# Granulobot_V10.net
KiCad netlist of a schematic drawn in EAGLE
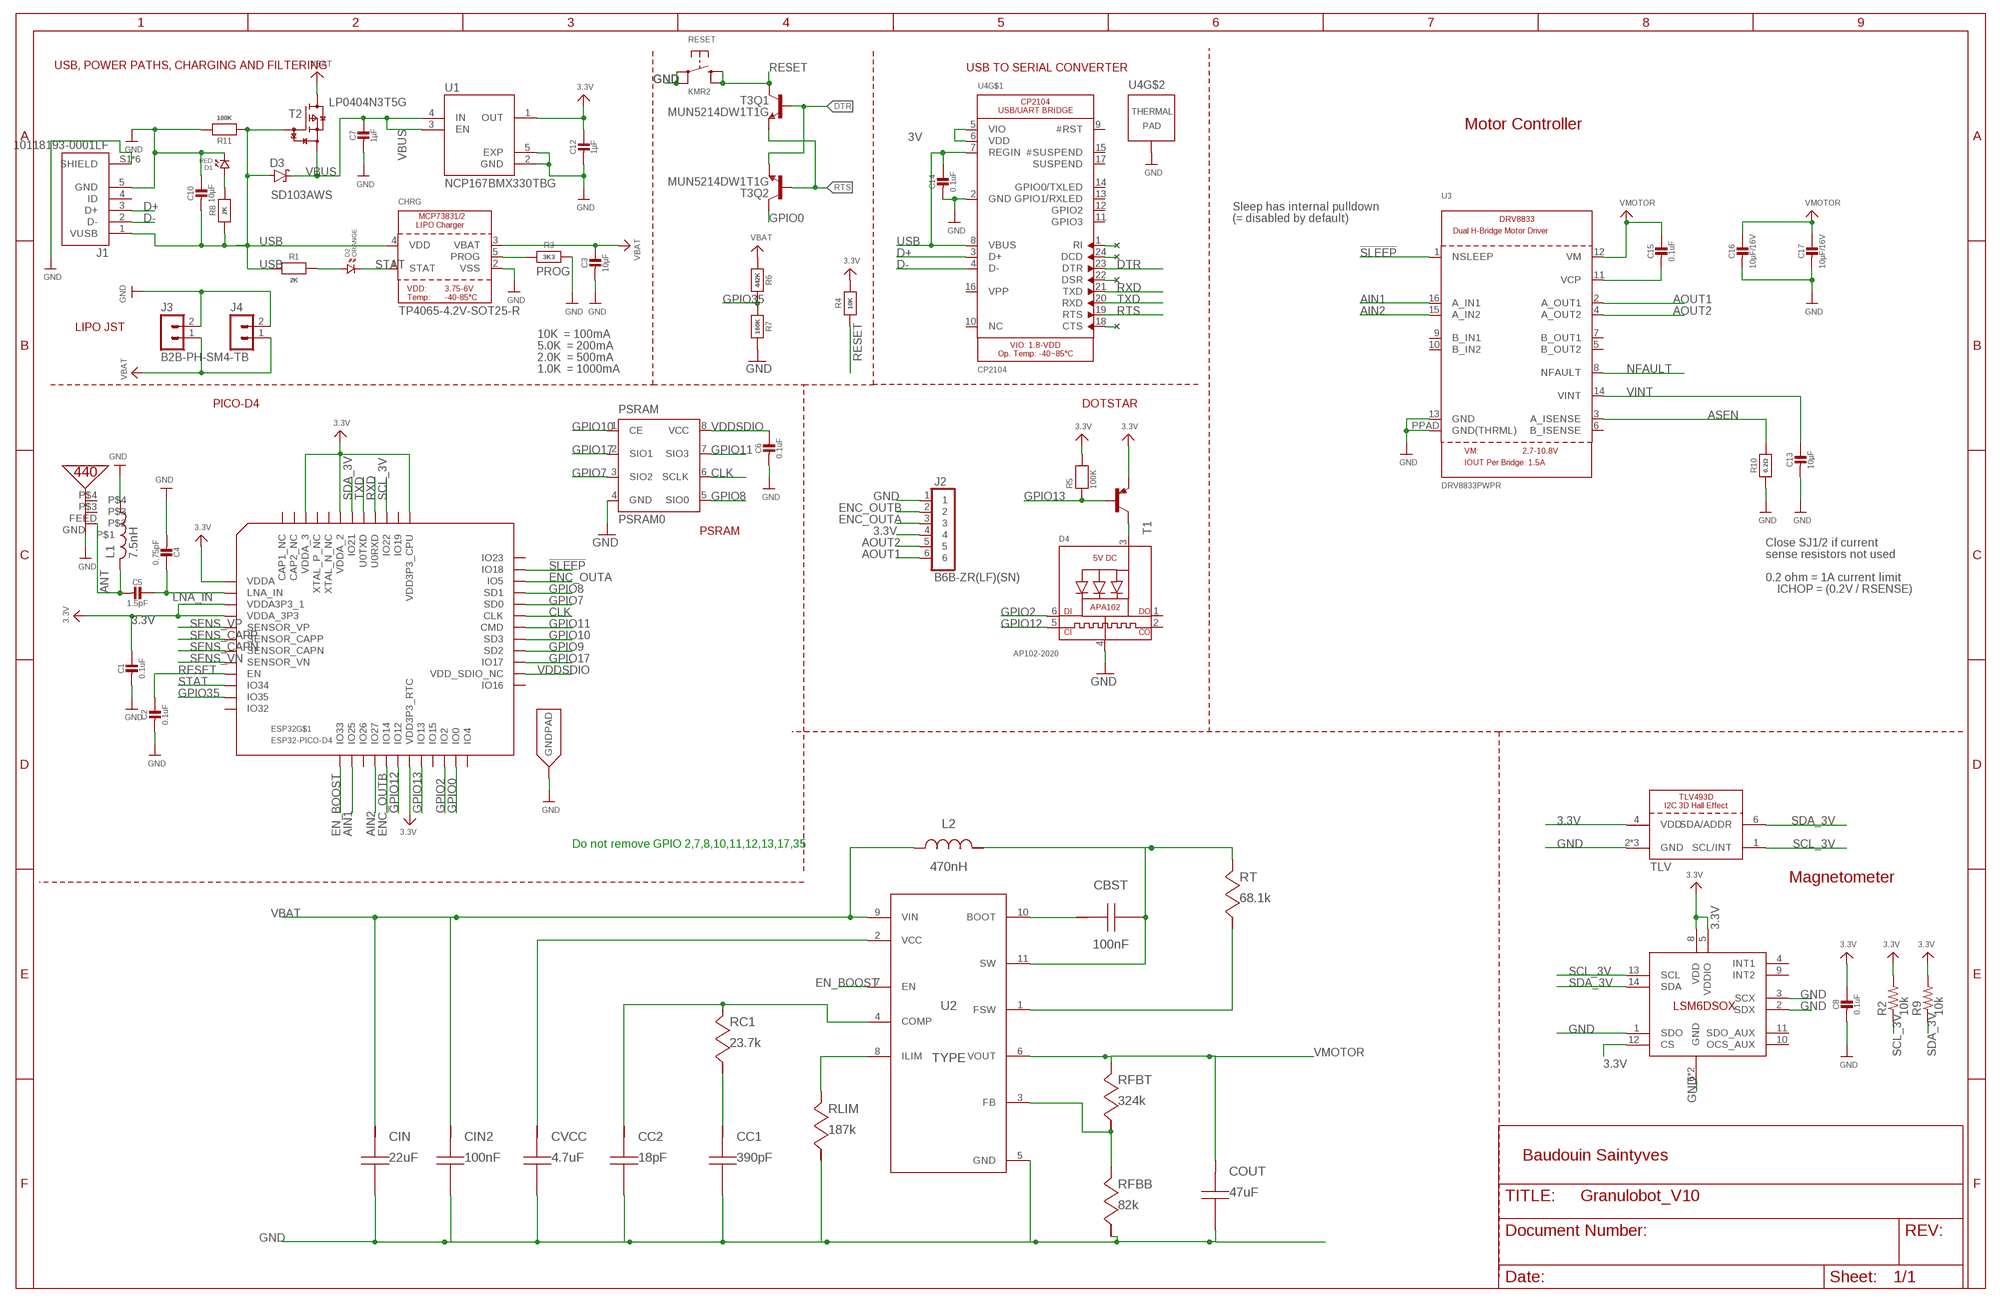
[diagram p0: schematic, sheet 1]

(export (version "E")
  (design (tool "Eeschema 10.0.6"))
  (components
    (comp (ref "ANT")
      (value "PRO-OB-440")
      (footprint "eagle-import:PRO-OB-440")
      (libsource (lib "eagle-import") (part "PRO-OB-440"))
    )
    (comp (ref "C1")
      (value "0.1uF")
      (footprint "eagle-import:_0402MP")
      (fields (field (name "MF") "MULTICOMP PRO") (field (name "MPN") "MC0402X104K250CT"))
      (libsource (lib "eagle-import") (part "CAP_CERAMIC_0402MP"))
    )
    (comp (ref "C2")
      (value "0.1uF")
      (footprint "eagle-import:_0402MP")
      (fields (field (name "MF") "MULTICOMP PRO") (field (name "MPN") "MC0402X104K250CT"))
      (libsource (lib "eagle-import") (part "CAP_CERAMIC_0402MP"))
    )
    (comp (ref "C3")
      (value "10µF")
      (footprint "eagle-import:_0603MP")
      (fields (field (name "MF") "SAMSUNG ELECTRO-MECHANICS") (field (name "MPN") "CL10A106KP8NNNC"))
      (libsource (lib "eagle-import") (part "CAP_CERAMIC_0603MP"))
    )
    (comp (ref "C4")
      (value "0.75pF")
      (footprint "eagle-import:_0402MP")
      (fields (field (name "MF") "MURATA") (field (name "MPN") "GJM1555C1HR75BB01D"))
      (libsource (lib "eagle-import") (part "CAP_CERAMIC_0402MP"))
    )
    (comp (ref "C5")
      (value "1.5pF")
      (footprint "eagle-import:_0402MP")
      (fields (field (name "MF") "TDK") (field (name "MPN") "C1005C0G1H1R5B050BA"))
      (libsource (lib "eagle-import") (part "CAP_CERAMIC_0402MP"))
    )
    (comp (ref "C6")
      (value "0.1uF")
      (footprint "eagle-import:_0402MP")
      (fields (field (name "MF") "MULTICOMP PRO") (field (name "MPN") "MC0402X104K250CT"))
      (libsource (lib "eagle-import") (part "CAP_CERAMIC_0402MP"))
    )
    (comp (ref "C7")
      (value "1µF")
      (footprint "eagle-import:_0402MP")
      (fields (field (name "MF") "MURATA") (field (name "MPN") "GRT155R70J105KE01D."))
      (libsource (lib "eagle-import") (part "CAP_CERAMIC_0402MP"))
    )
    (comp (ref "C8")
      (value "0.1uF")
      (footprint "eagle-import:0603-NO")
      (fields (field (name "MF") "MULTICOMP PRO") (field (name "MPN") "MCSH18B104K250CT"))
      (libsource (lib "eagle-import") (part "CAP_CERAMIC0603_NO"))
    )
    (comp (ref "C10")
      (value "10µF")
      (footprint "eagle-import:_0603MP")
      (fields (field (name "MF") "SAMSUNG ELECTRO-MECHANICS") (field (name "MPN") "CL10A106KP8NNNC"))
      (libsource (lib "eagle-import") (part "CAP_CERAMIC_0603MP"))
    )
    (comp (ref "C12")
      (value "1µF")
      (footprint "eagle-import:_0402MP")
      (fields (field (name "MF") "MURATA") (field (name "MPN") "GRT155R70J105KE01D."))
      (libsource (lib "eagle-import") (part "CAP_CERAMIC_0402MP"))
    )
    (comp (ref "C13")
      (value "10µF")
      (footprint "eagle-import:0805-NO")
      (fields (field (name "MF") "TAIYO YUDEN") (field (name "MPN") "LMK212BJ106KG-T"))
      (libsource (lib "eagle-import") (part "CAP_CERAMIC0805-NOOUTLINE"))
    )
    (comp (ref "C14")
      (value "0.1uF")
      (footprint "eagle-import:_0402MP")
      (fields (field (name "MF") "MULTICOMP PRO") (field (name "MPN") "MC0402X104K250CT"))
      (libsource (lib "eagle-import") (part "CAP_CERAMIC_0402MP"))
    )
    (comp (ref "C15")
      (value "0.1uF")
      (footprint "eagle-import:0805-NO")
      (fields (field (name "MF") "MULTICOMP PRO") (field (name "MPN") "MCSH21B104K100CT"))
      (libsource (lib "eagle-import") (part "CAP_CERAMIC0805-NOOUTLINE"))
    )
    (comp (ref "C16")
      (value "10µF/16V")
      (footprint "eagle-import:0805-NO")
      (fields (field (name "MF") "YAGEO") (field (name "MPN") "CC0805KKX5R8BB106"))
      (libsource (lib "eagle-import") (part "CAP_CERAMIC0805-NOOUTLINE"))
    )
    (comp (ref "C17")
      (value "10µF/16V")
      (footprint "eagle-import:0805-NO")
      (fields (field (name "MF") "YAGEO") (field (name "MPN") "CC0805KKX5R8BB106"))
      (libsource (lib "eagle-import") (part "CAP_CERAMIC0805-NOOUTLINE"))
    )
    (comp (ref "CBST")
      (value "100nF")
      (footprint "eagle-import:0402")
      (fields
        (field (name "MANUFACTURER_PART_NUMBER") "GRM155R71A104KA01D")
        (field (name "MF") "MULTICOMP PRO")
        (field (name "MPN") "MC0402X104K250CT")
      )
      (libsource (lib "eagle-import") (part "GRM155R71A104KA01D"))
    )
    (comp (ref "CC1")
      (value "390pF")
      (footprint "eagle-import:0402")
      (fields
        (field (name "MANUFACTURER_PART_NUMBER") "GRM1555C1H391JA01J")
        (field (name "MF") "MULTICOMP PRO")
        (field (name "MPN") "MC0402B391K250CT")
      )
      (libsource (lib "eagle-import") (part "GRM1555C1H391JA01J"))
    )
    (comp (ref "CC2")
      (value "18pF")
      (footprint "eagle-import:01005")
      (fields
        (field (name "MANUFACTURER_PART_NUMBER") "C0402C0G1C180J020BC")
        (field (name "MF") "MURATA")
        (field (name "MPN") "GRM0225C1E180GA02L")
      )
      (libsource (lib "eagle-import") (part "C0402C0G1C180J020BC"))
    )
    (comp (ref "CHRG")
      (value "TP4065-4.2V-SOT25-R")
      (footprint "eagle-import:SOT23-5")
      (libsource (lib "eagle-import") (part "MCP73831/2"))
    )
    (comp (ref "CIN")
      (value "22uF")
      (footprint "eagle-import:0805")
      (fields
        (field (name "MANUFACTURER_PART_NUMBER") "GRM21BR61A226ME44L")
        (field (name "MF") "KEMET")
        (field (name "MPN") "C1210C224J3GACTU")
      )
      (libsource (lib "eagle-import") (part "GRM21BR61A226ME44L"))
    )
    (comp (ref "CIN2")
      (value "100nF")
      (footprint "eagle-import:0402")
      (fields
        (field (name "MANUFACTURER_PART_NUMBER") "GRM155R71C104KA88D")
        (field (name "MF") "MULTICOMP PRO")
        (field (name "MPN") "MC0402X104K250CT")
      )
      (libsource (lib "eagle-import") (part "GRM155R71C104KA88D"))
    )
    (comp (ref "COUT")
      (value "47uF")
      (footprint "eagle-import:1206")
      (fields
        (field (name "MANUFACTURER_PART_NUMBER") "C3216X5R1E476M160AC")
        (field (name "MF") "KEMET")
        (field (name "MPN") "C0603C474K4PACTU")
      )
      (libsource (lib "eagle-import") (part "C3216X5R1E476M160ACC3216X5R1E476M160AC"))
    )
    (comp (ref "CVCC")
      (value "4.7uF")
      (footprint "eagle-import:0402_065")
      (fields
        (field (name "MANUFACTURER_PART_NUMBER") "GRM155R61A475MEAAD")
        (field (name "MF") "TAIYO YUDEN")
        (field (name "MPN") "JMK105BBJ475MV-F")
      )
      (libsource (lib "eagle-import") (part "GRM155R61A475MEAAD"))
    )
    (comp (ref "D1")
      (value "RED")
      (footprint "eagle-import:0402.LED")
      (fields (field (name "MF") "WURTH ELEKTRONIK") (field (name "MPN") "150040SS73220"))
      (libsource (lib "eagle-import") (part "LED.0402"))
    )
    (comp (ref "D2")
      (value "ORANGE")
      (footprint "eagle-import:0402.LED")
      (fields (field (name "MF") "DIALIGHT") (field (name "MPN") "5988A30107F"))
      (libsource (lib "eagle-import") (part "LED.0402"))
    )
    (comp (ref "D3")
      (value "BAT60J")
      (footprint "eagle-import:SOD323_ST")
      (fields (field (name "MF") "STMICROELECTRONICS") (field (name "MPN") "BAT60JFILM"))
      (libsource (lib "eagle-import") (part "BAT60J"))
    )
    (comp (ref "D4")
      (value "AP102-2020")
      (footprint "eagle-import:MICROBUILDER_APA102_2020")
      (libsource (lib "eagle-import") (part "MICROBUILDER_APA1022020"))
    )
    (comp (ref "ESP32")
      (value "ESP32-PICO-D4")
      (footprint "eagle-import:PICO-D4-QFN48")
      (fields (field (name "OC_NEWARK") "unknown"))
      (libsource (lib "eagle-import") (part "ESP32-PICO-D4"))
    )
    (comp (ref "J1")
      (value "10118193-0001LF")
      (footprint "eagle-import:FCI_10118193-0001LF")
      (fields (field (name "DIGI-KEY_PART_NUMBER") "609-4616-1-ND") (field (name "MF") "FCI"))
      (libsource (lib "eagle-import") (part "10118193-0001LF"))
    )
    (comp (ref "J2")
      (value "B6B-ZR(LF)(SN)")
      (footprint "eagle-import:JST_B6B-ZR(LF)(SN)")
      (fields (field (name "MF") "JST Sales"))
      (libsource (lib "eagle-import") (part "B6B-ZR(LF)(SN)"))
    )
    (comp (ref "J3")
      (value "B2B-PH-SM4-TB")
      (footprint "eagle-import:B2B-PH-SM4-TB")
      (fields
        (field (name "MF") "JST (JAPAN SOLDERLESS TERMINALS)")
        (field (name "MPN") "B2B-PH-SM4-TB(LF)(SN)")
      )
      (libsource (lib "eagle-import") (part "B2B-PH-SM4-TB"))
    )
    (comp (ref "J4")
      (value "B2B-PH-SM4-TB")
      (footprint "eagle-import:B2B-PH-SM4-TB")
      (fields
        (field (name "MF") "JST (JAPAN SOLDERLESS TERMINALS)")
        (field (name "MPN") "B2B-PH-SM4-TB(LF)(SN)")
      )
      (libsource (lib "eagle-import") (part "B2B-PH-SM4-TB"))
    )
    (comp (ref "L1")
      (value "7.5nH")
      (footprint "eagle-import:RESC0402_N")
      (fields (field (name "MF") "PANASONIC") (field (name "MPN") "ELJ-QF7N5JF"))
      (libsource (lib "eagle-import") (part "INDUCTOR_0402_N"))
    )
    (comp (ref "L2")
      (value "470nH")
      (footprint "eagle-import:IHLP-1212AE")
      (fields
        (field (name "MANUFACTURER") "Vishay")
        (field (name "MANUFACTURER_PART_NUMBER") "IHLP1212AEERR47M11")
        (field (name "MF") "VISHAY")
      )
      (libsource (lib "eagle-import") (part "IHLP1212AEERR47M11"))
    )
    (comp (ref "LSM6")
      (value "LSM6DSOX")
      (footprint "eagle-import:LGA-14L")
      (libsource (lib "eagle-import") (part "LSM6DSOX"))
    )
    (comp (ref "PSRAM")
      (value "PSRAM0")
      (footprint "eagle-import:SOP8")
      (fields (field (name "MPN") "BD6230F-E2") (field (name "MF") "ROHM"))
      (libsource (lib "eagle-import") (part "PSRAM0"))
    )
    (comp (ref "R1")
      (value "2K")
      (footprint "eagle-import:_0402MP")
      (fields (field (name "MF") "PANASONIC") (field (name "MPN") "ERJ-2RKF2001X"))
      (libsource (lib "eagle-import") (part "RESISTOR_0402MP"))
    )
    (comp (ref "R2")
      (value "10k")
      (footprint "eagle-import:R0603")
      (fields (field (name "MF") "NIC COMPONENTS") (field (name "MPN") "NRC-AS06F1002TRF"))
      (libsource (lib "eagle-import") (part "R-US_R0603"))
    )
    (comp (ref "R3")
      (value "3K3")
      (footprint "eagle-import:_0402MP")
      (fields (field (name "MF") "PANASONIC") (field (name "MPN") "ERJ-2RKF3301X"))
      (libsource (lib "eagle-import") (part "RESISTOR_0402MP"))
    )
    (comp (ref "R4")
      (value "10K")
      (footprint "eagle-import:_0402MP")
      (fields (field (name "MF") "PANASONIC") (field (name "MPN") "ERJ-2RKF1002X"))
      (libsource (lib "eagle-import") (part "RESISTOR_0402MP"))
    )
    (comp (ref "R5")
      (value "100K")
      (footprint "eagle-import:_0402MP")
      (fields (field (name "MF") "MULTICOMP PRO") (field (name "MPN") "MCWR04X1003FTL"))
      (libsource (lib "eagle-import") (part "RESISTOR_0402MP"))
    )
    (comp (ref "R6")
      (value "442K")
      (footprint "eagle-import:_0402MP")
      (fields (field (name "MF") "PANASONIC") (field (name "MPN") "ERJ-2RKF4423X"))
      (libsource (lib "eagle-import") (part "RESISTOR_0402MP"))
    )
    (comp (ref "R7")
      (value "160K")
      (footprint "eagle-import:_0402MP")
      (fields (field (name "MF") "VISHAY") (field (name "MPN") "CRCW0402160KFKED"))
      (libsource (lib "eagle-import") (part "RESISTOR_0402MP"))
    )
    (comp (ref "R8")
      (value "2K")
      (footprint "eagle-import:_0402MP")
      (fields (field (name "MF") "PANASONIC") (field (name "MPN") "ERJ-2RKF2001X"))
      (libsource (lib "eagle-import") (part "RESISTOR_0402MP"))
    )
    (comp (ref "R9")
      (value "10k")
      (footprint "eagle-import:R0603")
      (fields (field (name "MF") "NIC COMPONENTS") (field (name "MPN") "NRC-AS06F1002TRF"))
      (libsource (lib "eagle-import") (part "R-US_R0603"))
    )
    (comp (ref "R10")
      (value "0.2Ω")
      (footprint "eagle-import:_1206")
      (fields (field (name "MF") "OHMITE") (field (name "MPN") "KDV12FR200ET"))
      (libsource (lib "eagle-import") (part "RESISTOR_1206"))
    )
    (comp (ref "R11")
      (value "100K")
      (footprint "eagle-import:_0402MP")
      (fields (field (name "MF") "MULTICOMP PRO") (field (name "MPN") "MCWR04X1003FTL"))
      (libsource (lib "eagle-import") (part "RESISTOR_0402MP"))
    )
    (comp (ref "RC1")
      (value "23.7k")
      (footprint "eagle-import:0201")
      (fields
        (field (name "MANUFACTURER_PART_NUMBER") "RC0201FR0723K7L")
        (field (name "POWER") "0.05")
        (field (name "TOLERANCE") "1.0")
      )
      (libsource (lib "eagle-import") (part "RC0201FR-0723K7L"))
    )
    (comp (ref "RESET")
      (value "KMR2")
      (footprint "eagle-import:BTN_KMR2_4.6X2.8")
      (fields (field (name "MF") "C & K COMPONENTS") (field (name "MPN") "KMR231G LFS"))
      (libsource (lib "eagle-import") (part "SWITCH_TACT_SMT4.6X2.8"))
    )
    (comp (ref "RFBB")
      (value "82k")
      (footprint "eagle-import:0603")
      (fields
        (field (name "MANUFACTURER_PART_NUMBER") "RC0603FR0782KL")
        (field (name "POWER") "0.1")
        (field (name "TOLERANCE") "1.0")
      )
      (libsource (lib "eagle-import") (part "RC0603FR-0782KL"))
    )
    (comp (ref "RFBT")
      (value "324k")
      (footprint "eagle-import:0402")
      (fields
        (field (name "MANUFACTURER_PART_NUMBER") "CRCW0402324KFKED")
        (field (name "POWER") "0.063")
        (field (name "TOLERANCE") "1.0")
      )
      (libsource (lib "eagle-import") (part "CRCW0402324KFKED"))
    )
    (comp (ref "RLIM")
      (value "187k")
      (footprint "eagle-import:0402")
      (fields
        (field (name "MANUFACTURER_PART_NUMBER") "CRCW0402187KFKED")
        (field (name "POWER") "0.063")
        (field (name "TOLERANCE") "1.0")
      )
      (libsource (lib "eagle-import") (part "CRCW0402187KFKED"))
    )
    (comp (ref "RT")
      (value "68.1k")
      (footprint "eagle-import:0201")
      (fields
        (field (name "MANUFACTURER_PART_NUMBER") "CRCW020168K1FKED")
        (field (name "POWER") "0.05")
        (field (name "TOLERANCE") "1.0")
      )
      (libsource (lib "eagle-import") (part "CRCW020168K1FKED"))
    )
    (comp (ref "T1")
      (value "TINYPICO-PNPAMB")
      (footprint "eagle-import:SOT883(B)")
      (libsource (lib "eagle-import") (part "TINYPICO-PNPMBA"))
    )
    (comp (ref "T2")
      (value "TINYPICO-P-FETKMB")
      (footprint "eagle-import:SOT883(B)")
      (libsource (lib "eagle-import") (part "TINYPICO-P-FETMBK"))
    )
    (comp (ref "T3")
      (value "MUN5214DW1T1G")
      (footprint "eagle-import:DUAL_NPN_SC70-6")
      (fields
        (field (name "MF") "ON SEMICONDUCTOR")
        (field (name "MPN") "MUN5214DW1T1G")
        (field (name "OC_NEWARK") "10N9540")
      )
      (libsource (lib "eagle-import") (part "MBT3904DW1T1"))
    )
    (comp (ref "TLV")
      (value "TLV493D")
      (footprint "eagle-import:SOT23-6")
      (fields (field (name "MF") "INFINEON") (field (name "MPN") "TLV493DA1B6HTSA2"))
      (libsource (lib "eagle-import") (part "TLV493D"))
    )
    (comp (ref "U1")
      (value "NCP170AMX300TCG")
      (footprint "eagle-import:VREG_NCP170AMX300TCG")
      (fields (field (name "MF") "ON Semiconductor"))
      (libsource (lib "eagle-import") (part "NCP170AMX300TCG"))
    )
    (comp (ref "U2")
      (value "Value")
      (footprint "eagle-import:RNR0011A")
      (fields
        (field (name "MANUFACTURER") "Texas Instruments")
        (field (name "MANUFACTURER_PART_NUMBER") "TPS61089RNRR")
        (field (name "TYPE") "TYPE")
      )
      (libsource (lib "eagle-import") (part "TPS61089RNRR"))
    )
    (comp (ref "U3")
      (value "DRV8833PWPR")
      (footprint "eagle-import:HTSSOP16")
      (fields (field (name "MF") "TEXAS INSTRUMENTS"))
      (libsource (lib "eagle-import") (part "DRV8833"))
    )
    (comp (ref "U4")
      (value "CP2104")
      (footprint "eagle-import:MICROBUILDER_QFN24_4MM_SMSC")
      (fields
        (field (name "MF") "SILICON LABS")
        (field (name "MPN") "CP2104-F03-GMR")
        (field (name "OC_NEWARK") "74AC8649")
      )
      (libsource (lib "eagle-import") (part "MICROBUILDER_CP2104"))
    )
  )
  (nets
    (net (code "1") (name "/3V") (class "Default")
      (node (ref "U4") (pin "5") (pinfunction "VIO_5") (pintype "power_in"))
      (node (ref "U4") (pin "6") (pinfunction "VDD_6") (pintype "power_in"))
    )
    (net (code "2") (name "/AIN1") (class "Default")
      (node (ref "ESP32") (pin "14") (pinfunction "IO25_14") (pintype "bidirectional"))
      (node (ref "U3") (pin "16") (pinfunction "A_IN1_16") (pintype "input"))
    )
    (net (code "3") (name "/AIN2") (class "Default")
      (node (ref "ESP32") (pin "16") (pinfunction "IO27_16") (pintype "bidirectional"))
      (node (ref "U3") (pin "15") (pinfunction "A_IN2_15") (pintype "input"))
    )
    (net (code "4") (name "/ANT") (class "Default")
      (node (ref "ANT") (pin "FEED") (pinfunction "P$2_FEED") (pintype "input"))
      (node (ref "C5") (pin "2") (pinfunction "2_2") (pintype "passive"))
      (node (ref "L1") (pin "2") (pinfunction "2_2") (pintype "passive"))
    )
    (net (code "5") (name "/AOUT1") (class "Default")
      (node (ref "J2") (pin "6") (pinfunction "6_6") (pintype "passive"))
      (node (ref "U3") (pin "2") (pinfunction "A_OUT1_2") (pintype "output"))
    )
    (net (code "6") (name "/AOUT2") (class "Default")
      (node (ref "J2") (pin "5") (pinfunction "5_5") (pintype "passive"))
      (node (ref "U3") (pin "4") (pinfunction "A_OUT2_4") (pintype "output"))
    )
    (net (code "7") (name "/ASEN") (class "Default")
      (node (ref "R10") (pin "2") (pinfunction "2_2") (pintype "passive"))
      (node (ref "U3") (pin "3") (pinfunction "A_ISENSE_3") (pintype "bidirectional"))
    )
    (net (code "8") (name "/CLK") (class "Default")
      (node (ref "ESP32") (pin "31") (pinfunction "CLK_31") (pintype "bidirectional"))
      (node (ref "PSRAM") (pin "6") (pinfunction "SCLK_6") (pintype "passive"))
    )
    (net (code "9") (name "/D+") (class "Default")
      (node (ref "J1") (pin "3") (pinfunction "D+_3") (pintype "passive"))
      (node (ref "U4") (pin "3") (pinfunction "D+_3") (pintype "bidirectional"))
    )
    (net (code "10") (name "/D-") (class "Default")
      (node (ref "J1") (pin "2") (pinfunction "D-_2") (pintype "passive"))
      (node (ref "U4") (pin "4") (pinfunction "D-_4") (pintype "bidirectional"))
    )
    (net (code "11") (name "/ENC_OUTA") (class "Default")
      (node (ref "ESP32") (pin "34") (pinfunction "IO5_34") (pintype "bidirectional"))
      (node (ref "J2") (pin "3") (pinfunction "3_3") (pintype "passive"))
    )
    (net (code "12") (name "/ENC_OUTB") (class "Default")
      (node (ref "ESP32") (pin "17") (pinfunction "IO14_17") (pintype "bidirectional"))
      (node (ref "J2") (pin "2") (pinfunction "2_2") (pintype "passive"))
    )
    (net (code "13") (name "/EN_BOOST") (class "Default")
      (node (ref "ESP32") (pin "13") (pinfunction "IO33_13") (pintype "bidirectional"))
      (node (ref "U2") (pin "7") (pinfunction "EN_7") (pintype "input"))
    )
    (net (code "14") (name "/GPIO0") (class "Default")
      (node (ref "ESP32") (pin "23") (pinfunction "IO0_23") (pintype "bidirectional"))
      (node (ref "T3") (pin "6") (pinfunction "C_6") (pintype "passive"))
    )
    (net (code "15") (name "/GPIO2") (class "Default")
      (node (ref "D4") (pin "6") (pinfunction "DI_6") (pintype "input"))
      (node (ref "ESP32") (pin "22") (pinfunction "IO2_22") (pintype "bidirectional"))
    )
    (net (code "16") (name "/GPIO7") (class "Default")
      (node (ref "ESP32") (pin "32") (pinfunction "SD0_32") (pintype "bidirectional"))
      (node (ref "PSRAM") (pin "3") (pinfunction "SIO2_3") (pintype "power_in"))
    )
    (net (code "17") (name "/GPIO8") (class "Default")
      (node (ref "ESP32") (pin "33") (pinfunction "SD1_33") (pintype "bidirectional"))
      (node (ref "PSRAM") (pin "5") (pinfunction "SIO0_5") (pintype "input"))
    )
    (net (code "18") (name "/GPIO9") (class "Default")
      (node (ref "ESP32") (pin "28") (pinfunction "SD2_28") (pintype "bidirectional"))
    )
    (net (code "19") (name "/GPIO10") (class "Default")
      (node (ref "ESP32") (pin "29") (pinfunction "SD3_29") (pintype "bidirectional"))
      (node (ref "PSRAM") (pin "1") (pinfunction "CE_1") (pintype "output"))
    )
    (net (code "20") (name "/GPIO11") (class "Default")
      (node (ref "ESP32") (pin "30") (pinfunction "CMD_30") (pintype "bidirectional"))
      (node (ref "PSRAM") (pin "7") (pinfunction "SIO3_7") (pintype "output"))
    )
    (net (code "21") (name "/GPIO12") (class "Default")
      (node (ref "D4") (pin "5") (pinfunction "CKI_5") (pintype "input"))
      (node (ref "ESP32") (pin "18") (pinfunction "IO12_18") (pintype "power_in"))
    )
    (net (code "22") (name "/GPIO13") (class "Default")
      (node (ref "ESP32") (pin "20") (pinfunction "IO13_20") (pintype "bidirectional"))
      (node (ref "R5") (pin "1") (pinfunction "1_1") (pintype "passive"))
      (node (ref "T1") (pin "1") (pinfunction "B_1") (pintype "passive"))
    )
    (net (code "23") (name "/GPIO17") (class "Default")
      (node (ref "ESP32") (pin "27") (pinfunction "IO17_27") (pintype "bidirectional"))
      (node (ref "PSRAM") (pin "2") (pinfunction "SIO1_2") (pintype "power_in"))
    )
    (net (code "24") (name "/GPIO35") (class "Default")
      (node (ref "ESP32") (pin "11") (pinfunction "IO35_11") (pintype "bidirectional"))
      (node (ref "R6") (pin "2") (pinfunction "2_2") (pintype "passive"))
      (node (ref "R7") (pin "1") (pinfunction "1_1") (pintype "passive"))
    )
    (net (code "25") (name "/LNA_IN") (class "Default")
      (node (ref "C4") (pin "1") (pinfunction "1_1") (pintype "passive"))
      (node (ref "C5") (pin "1") (pinfunction "1_1") (pintype "passive"))
      (node (ref "ESP32") (pin "2") (pinfunction "LNA_IN_2") (pintype "bidirectional"))
    )
    (net (code "26") (name "/NFAULT") (class "Default")
      (node (ref "U3") (pin "8") (pinfunction "NFAULT_8") (pintype "bidirectional"))
    )
    (net (code "27") (name "/PROG") (class "Default")
      (node (ref "CHRG") (pin "5") (pinfunction "PROG_5") (pintype "input"))
      (node (ref "R3") (pin "1") (pinfunction "1_1") (pintype "passive"))
    )
    (net (code "28") (name "/RESET") (class "Default")
      (node (ref "C2") (pin "1") (pinfunction "1_1") (pintype "passive"))
      (node (ref "ESP32") (pin "9") (pinfunction "EN_9") (pintype "bidirectional"))
      (node (ref "R4") (pin "1") (pinfunction "1_1") (pintype "passive"))
      (node (ref "RESET") (pin "B") (pinfunction "S_B") (pintype "passive"))
      (node (ref "RESET") (pin "B'") (pinfunction "S1_B'") (pintype "passive"))
      (node (ref "T3") (pin "3") (pinfunction "C_3") (pintype "passive"))
    )
    (net (code "29") (name "/RXD") (class "Default")
      (node (ref "ESP32") (pin "40") (pinfunction "U0RXD_40") (pintype "bidirectional"))
      (node (ref "U4") (pin "21") (pinfunction "TXD_21") (pintype "output"))
    )
    (net (code "30") (name "/SCL_3V") (class "Default")
      (node (ref "ESP32") (pin "39") (pinfunction "IO22_39") (pintype "bidirectional"))
      (node (ref "LSM6") (pin "13") (pinfunction "SCL_13") (pintype "bidirectional"))
      (node (ref "R2") (pin "1") (pinfunction "1_1") (pintype "passive"))
      (node (ref "TLV") (pin "1") (pinfunction "SCL/INT_1") (pintype "bidirectional"))
    )
    (net (code "31") (name "/SDA_3V") (class "Default")
      (node (ref "ESP32") (pin "42") (pinfunction "IO21_42") (pintype "power_in"))
      (node (ref "LSM6") (pin "14") (pinfunction "SDA_14") (pintype "bidirectional"))
      (node (ref "R9") (pin "1") (pinfunction "1_1") (pintype "passive"))
      (node (ref "TLV") (pin "6") (pinfunction "SDA/ADDR_6") (pintype "bidirectional"))
    )
    (net (code "32") (name "/SENS_CAPN") (class "Default")
      (node (ref "ESP32") (pin "7") (pinfunction "SENSOR_CAPN_7") (pintype "power_in"))
    )
    (net (code "33") (name "/SENS_CAPP") (class "Default")
      (node (ref "ESP32") (pin "6") (pinfunction "SENSOR_CAPP_6") (pintype "bidirectional"))
    )
    (net (code "34") (name "/SENS_VN") (class "Default")
      (node (ref "ESP32") (pin "8") (pinfunction "SENSOR_VN_8") (pintype "bidirectional"))
    )
    (net (code "35") (name "/SENS_VP") (class "Default")
      (node (ref "ESP32") (pin "5") (pinfunction "SENSOR_VP_5") (pintype "bidirectional"))
    )
    (net (code "36") (name "/STAT") (class "Default")
      (node (ref "CHRG") (pin "1") (pinfunction "STAT_1") (pintype "output"))
      (node (ref "D2") (pin "P$2") (pinfunction "2_P$2") (pintype "bidirectional"))
      (node (ref "ESP32") (pin "10") (pinfunction "IO34_10") (pintype "bidirectional"))
    )
    (net (code "37") (name "/TXD") (class "Default")
      (node (ref "ESP32") (pin "41") (pinfunction "U0TXD_41") (pintype "bidirectional"))
      (node (ref "U4") (pin "20") (pinfunction "RXD_20") (pintype "input"))
    )
    (net (code "38") (name "/USB") (class "Default")
      (node (ref "C10") (pin "2") (pinfunction "2_2") (pintype "passive"))
      (node (ref "C14") (pin "1") (pinfunction "1_1") (pintype "passive"))
      (node (ref "CHRG") (pin "4") (pinfunction "VDD_4") (pintype "power_in"))
      (node (ref "D3") (pin "A") (pinfunction "A_A") (pintype "passive"))
      (node (ref "J1") (pin "1") (pinfunction "VUSB_1") (pintype "passive"))
      (node (ref "R1") (pin "1") (pinfunction "1_1") (pintype "passive"))
      (node (ref "R11") (pin "1") (pinfunction "1_1") (pintype "passive"))
      (node (ref "R8") (pin "1") (pinfunction "1_1") (pintype "passive"))
      (node (ref "T2") (pin "1") (pinfunction "G_1") (pintype "passive"))
      (node (ref "U4") (pin "7") (pinfunction "REGIN_7") (pintype "power_in"))
      (node (ref "U4") (pin "8") (pinfunction "VBUS_8") (pintype "power_in"))
    )
    (net (code "39") (name "/VBUS") (class "Default")
      (node (ref "C7") (pin "1") (pinfunction "1_1") (pintype "passive"))
      (node (ref "D3") (pin "C") (pinfunction "C_C") (pintype "passive"))
      (node (ref "T2") (pin "2") (pinfunction "S_2") (pintype "passive"))
      (node (ref "U1") (pin "3") (pinfunction "EN_3") (pintype "input"))
      (node (ref "U1") (pin "4") (pinfunction "IN_4") (pintype "input"))
    )
    (net (code "40") (name "/VDDSDIO") (class "Default")
      (node (ref "C6") (pin "1") (pinfunction "1_1") (pintype "passive"))
      (node (ref "ESP32") (pin "26") (pinfunction "VDD_SDIO_NC_26") (pintype "bidirectional"))
      (node (ref "PSRAM") (pin "8") (pinfunction "VCC_8") (pintype "power_in"))
    )
    (net (code "41") (name "/VINT") (class "Default")
      (node (ref "C13") (pin "1") (pinfunction "1_1") (pintype "passive"))
      (node (ref "U3") (pin "14") (pinfunction "VINT_14") (pintype "power_in"))
    )
    (net (code "42") (name "/~{SLEEP}") (class "Default")
      (node (ref "ESP32") (pin "35") (pinfunction "IO18_35") (pintype "bidirectional"))
      (node (ref "U3") (pin "1") (pinfunction "NSLEEP_1") (pintype "input"))
    )
    (net (code "43") (name "3.3V") (class "Default")
      (node (ref "C1") (pin "1") (pinfunction "1_1") (pintype "passive"))
      (node (ref "C12") (pin "1") (pinfunction "1_1") (pintype "passive"))
      (node (ref "C8") (pin "1") (pinfunction "1_1") (pintype "passive"))
      (node (ref "ESP32") (pin "1") (pinfunction "VDDA_1") (pintype "bidirectional"))
      (node (ref "ESP32") (pin "19") (pinfunction "VDD3P3_RTC_19") (pintype "bidirectional"))
      (node (ref "ESP32") (pin "3") (pinfunction "VDDA3P3_1_3") (pintype "bidirectional"))
      (node (ref "ESP32") (pin "37") (pinfunction "VDD3P3_CPU_37") (pintype "bidirectional"))
      (node (ref "ESP32") (pin "4") (pinfunction "VDDA_3P3_4") (pintype "bidirectional"))
      (node (ref "ESP32") (pin "43") (pinfunction "VDDA_2_43") (pintype "bidirectional"))
      (node (ref "ESP32") (pin "46") (pinfunction "VDDA_3_46") (pintype "bidirectional"))
      (node (ref "J2") (pin "4") (pinfunction "4_4") (pintype "passive"))
      (node (ref "LSM6") (pin "12") (pinfunction "CS_12") (pintype "bidirectional"))
      (node (ref "LSM6") (pin "5") (pinfunction "VDDIO_5") (pintype "power_in"))
      (node (ref "LSM6") (pin "8") (pinfunction "VDD_8") (pintype "power_in"))
      (node (ref "R2") (pin "2") (pinfunction "2_2") (pintype "passive"))
      (node (ref "R4") (pin "2") (pinfunction "2_2") (pintype "passive"))
      (node (ref "R5") (pin "2") (pinfunction "2_2") (pintype "passive"))
      (node (ref "R9") (pin "2") (pinfunction "2_2") (pintype "passive"))
      (node (ref "T1") (pin "2") (pinfunction "E_2") (pintype "passive"))
      (node (ref "TLV") (pin "4") (pinfunction "VDD_4") (pintype "power_in"))
      (node (ref "U1") (pin "1") (pinfunction "OUT_1") (pintype "output"))
    )
    (net (code "44") (name "DTR") (class "Default")
      (node (ref "T3") (pin "1") (pinfunction "E_1") (pintype "passive"))
      (node (ref "T3") (pin "5") (pinfunction "B_5") (pintype "passive"))
      (node (ref "U4") (pin "23") (pinfunction "DTR_23") (pintype "output"))
    )
    (net (code "45") (name "GND") (class "Default")
      (node (ref "ANT") (pin "GND") (pinfunction "P$1_GND") (pintype "input"))
      (node (ref "C1") (pin "2") (pinfunction "2_2") (pintype "passive"))
      (node (ref "C10") (pin "1") (pinfunction "1_1") (pintype "passive"))
      (node (ref "C12") (pin "2") (pinfunction "2_2") (pintype "passive"))
      (node (ref "C13") (pin "2") (pinfunction "2_2") (pintype "passive"))
      (node (ref "C14") (pin "2") (pinfunction "2_2") (pintype "passive"))
      (node (ref "C16") (pin "2") (pinfunction "2_2") (pintype "passive"))
      (node (ref "C17") (pin "2") (pinfunction "2_2") (pintype "passive"))
      (node (ref "C2") (pin "2") (pinfunction "2_2") (pintype "passive"))
      (node (ref "C3") (pin "2") (pinfunction "2_2") (pintype "passive"))
      (node (ref "C4") (pin "2") (pinfunction "2_2") (pintype "passive"))
      (node (ref "C6") (pin "2") (pinfunction "2_2") (pintype "passive"))
      (node (ref "C7") (pin "2") (pinfunction "2_2") (pintype "passive"))
      (node (ref "C8") (pin "2") (pinfunction "2_2") (pintype "passive"))
      (node (ref "CC1") (pin "2") (pinfunction "2_2") (pintype "passive"))
      (node (ref "CC2") (pin "2") (pinfunction "2_2") (pintype "passive"))
      (node (ref "CHRG") (pin "2") (pinfunction "VSS_2") (pintype "power_in"))
      (node (ref "CIN") (pin "2") (pinfunction "2_2") (pintype "passive"))
      (node (ref "CIN2") (pin "2") (pinfunction "2_2") (pintype "passive"))
      (node (ref "COUT") (pin "2") (pinfunction "2_2") (pintype "passive"))
      (node (ref "CVCC") (pin "2") (pinfunction "2_2") (pintype "passive"))
      (node (ref "D1") (pin "P$2") (pinfunction "2_P$2") (pintype "bidirectional"))
      (node (ref "D4") (pin "4") (pinfunction "GND_4") (pintype "power_in"))
      (node (ref "ESP32") (pin "EXP") (pinfunction "GNDPAD_EXP") (pintype "power_in"))
      (node (ref "J1") (pin "5") (pinfunction "GND_5") (pintype "passive"))
      (node (ref "J1") (pin "S1") (pinfunction "SHIELD_S1") (pintype "passive"))
      (node (ref "J1") (pin "S2") (pinfunction "SHIELD_S2") (pintype "passive"))
      (node (ref "J1") (pin "S3") (pinfunction "SHIELD_S3") (pintype "passive"))
      (node (ref "J1") (pin "S4") (pinfunction "SHIELD_S4") (pintype "passive"))
      (node (ref "J1") (pin "S5") (pinfunction "SHIELD_S5") (pintype "passive"))
      (node (ref "J1") (pin "S6") (pinfunction "SHIELD_S6") (pintype "passive"))
      (node (ref "J2") (pin "1") (pinfunction "1_1") (pintype "passive"))
      (node (ref "J3") (pin "2") (pinfunction "2_2") (pintype "passive"))
      (node (ref "J4") (pin "2") (pinfunction "2_2") (pintype "passive"))
      (node (ref "L1") (pin "1") (pinfunction "1_1") (pintype "passive"))
      (node (ref "LSM6") (pin "1") (pinfunction "SDO_1") (pintype "bidirectional"))
      (node (ref "LSM6") (pin "2") (pinfunction "SDX_2") (pintype "bidirectional"))
      (node (ref "LSM6") (pin "3") (pinfunction "SCX_3") (pintype "bidirectional"))
      (node (ref "LSM6") (pin "6") (pinfunction "GND_6") (pintype "power_in"))
      (node (ref "LSM6") (pin "7") (pinfunction "GND_7") (pintype "power_in"))
      (node (ref "PSRAM") (pin "4") (pinfunction "GND_4") (pintype "input"))
      (node (ref "R10") (pin "1") (pinfunction "1_1") (pintype "passive"))
      (node (ref "R11") (pin "2") (pinfunction "2_2") (pintype "passive"))
      (node (ref "R3") (pin "2") (pinfunction "2_2") (pintype "passive"))
      (node (ref "R7") (pin "2") (pinfunction "2_2") (pintype "passive"))
      (node (ref "RESET") (pin "A") (pinfunction "P_A") (pintype "passive"))
      (node (ref "RESET") (pin "A'") (pinfunction "P1_A'") (pintype "passive"))
      (node (ref "RFBB") (pin "2") (pinfunction "2_2") (pintype "passive"))
      (node (ref "RLIM") (pin "2") (pinfunction "2_2") (pintype "passive"))
      (node (ref "TLV") (pin "2") (pinfunction "GND_2") (pintype "power_in"))
      (node (ref "TLV") (pin "3") (pinfunction "GND_3") (pintype "power_in"))
      (node (ref "TLV") (pin "5") (pinfunction "GND_5") (pintype "power_in"))
      (node (ref "U1") (pin "2") (pinfunction "GND_2") (pintype "power_in"))
      (node (ref "U1") (pin "5") (pinfunction "EXP_5") (pintype "power_in"))
      (node (ref "U2") (pin "5") (pinfunction "GND_5") (pintype "power_in"))
      (node (ref "U3") (pin "13") (pinfunction "GND_13") (pintype "power_in"))
      (node (ref "U3") (pin "PPAD") (pinfunction "GND(THRML)_PPAD") (pintype "power_in"))
      (node (ref "U4") (pin "2") (pinfunction "GND_2") (pintype "power_in"))
      (node (ref "U4") (pin "THERM") (pinfunction "TP_THERM") (pintype "power_in"))
    )
    (net (code "46") (name "Net-(CC1-Pad1)") (class "Default")
      (node (ref "CC1") (pin "1") (pinfunction "1_1") (pintype "passive"))
      (node (ref "RC1") (pin "2") (pinfunction "2_2") (pintype "passive"))
    )
    (net (code "47") (name "Net-(D1-1)") (class "Default")
      (node (ref "D1") (pin "P$1") (pinfunction "1_P$1") (pintype "bidirectional"))
      (node (ref "R8") (pin "2") (pinfunction "2_2") (pintype "passive"))
    )
    (net (code "48") (name "Net-(D2-1)") (class "Default")
      (node (ref "D2") (pin "P$1") (pinfunction "1_P$1") (pintype "bidirectional"))
      (node (ref "R1") (pin "2") (pinfunction "2_2") (pintype "passive"))
    )
    (net (code "49") (name "Net-(D4-VDD)") (class "Default")
      (node (ref "D4") (pin "3") (pinfunction "VDD_3") (pintype "power_in"))
      (node (ref "T1") (pin "3") (pinfunction "C_3") (pintype "passive"))
    )
    (net (code "50") (name "Net-(U2-BOOT)") (class "Default")
      (node (ref "CBST") (pin "1") (pinfunction "1_1") (pintype "passive"))
      (node (ref "U2") (pin "10") (pinfunction "BOOT_10") (pintype "power_in"))
    )
    (net (code "51") (name "Net-(U2-COMP)") (class "Default")
      (node (ref "CC2") (pin "1") (pinfunction "1_1") (pintype "passive"))
      (node (ref "RC1") (pin "1") (pinfunction "1_1") (pintype "passive"))
      (node (ref "U2") (pin "4") (pinfunction "COMP_4") (pintype "output"))
    )
    (net (code "52") (name "Net-(U2-FB)") (class "Default")
      (node (ref "RFBB") (pin "1") (pinfunction "1_1") (pintype "passive"))
      (node (ref "RFBT") (pin "2") (pinfunction "2_2") (pintype "passive"))
      (node (ref "U2") (pin "3") (pinfunction "FB_3") (pintype "input"))
    )
    (net (code "53") (name "Net-(U2-FSW)") (class "Default")
      (node (ref "RT") (pin "2") (pinfunction "2_2") (pintype "passive"))
      (node (ref "U2") (pin "1") (pinfunction "FSW_1") (pintype "input"))
    )
    (net (code "54") (name "Net-(U2-ILIM)") (class "Default")
      (node (ref "RLIM") (pin "1") (pinfunction "1_1") (pintype "passive"))
      (node (ref "U2") (pin "8") (pinfunction "ILIM_8") (pintype "input"))
    )
    (net (code "55") (name "Net-(U2-SW)") (class "Default")
      (node (ref "CBST") (pin "2") (pinfunction "2_2") (pintype "passive"))
      (node (ref "L2") (pin "2") (pinfunction "2_2") (pintype "passive"))
      (node (ref "RT") (pin "1") (pinfunction "1_1") (pintype "passive"))
      (node (ref "U2") (pin "11") (pinfunction "SW_11") (pintype "power_in"))
    )
    (net (code "56") (name "Net-(U2-VCC)") (class "Default")
      (node (ref "CVCC") (pin "1") (pinfunction "1_1") (pintype "passive"))
      (node (ref "U2") (pin "2") (pinfunction "VCC_2") (pintype "power_in"))
    )
    (net (code "57") (name "Net-(U3-VCP)") (class "Default")
      (node (ref "C15") (pin "2") (pinfunction "2_2") (pintype "passive"))
      (node (ref "U3") (pin "11") (pinfunction "VCP_11") (pintype "bidirectional"))
    )
    (net (code "58") (name "RTS") (class "Default")
      (node (ref "T3") (pin "2") (pinfunction "B_2") (pintype "passive"))
      (node (ref "T3") (pin "4") (pinfunction "E_4") (pintype "passive"))
      (node (ref "U4") (pin "19") (pinfunction "RTS_19") (pintype "output"))
    )
    (net (code "59") (name "VBAT") (class "Default")
      (node (ref "C3") (pin "1") (pinfunction "1_1") (pintype "passive"))
      (node (ref "CHRG") (pin "3") (pinfunction "VBAT_3") (pintype "power_in"))
      (node (ref "CIN") (pin "1") (pinfunction "1_1") (pintype "passive"))
      (node (ref "CIN2") (pin "1") (pinfunction "1_1") (pintype "passive"))
      (node (ref "J3") (pin "1") (pinfunction "1_1") (pintype "passive"))
      (node (ref "J4") (pin "1") (pinfunction "1_1") (pintype "passive"))
      (node (ref "L2") (pin "1") (pinfunction "1_1") (pintype "passive"))
      (node (ref "R6") (pin "1") (pinfunction "1_1") (pintype "passive"))
      (node (ref "T2") (pin "3") (pinfunction "D_3") (pintype "passive"))
      (node (ref "U2") (pin "9") (pinfunction "VIN_9") (pintype "power_in"))
    )
    (net (code "60") (name "VMOTOR") (class "Default")
      (node (ref "C15") (pin "1") (pinfunction "1_1") (pintype "passive"))
      (node (ref "C16") (pin "1") (pinfunction "1_1") (pintype "passive"))
      (node (ref "C17") (pin "1") (pinfunction "1_1") (pintype "passive"))
      (node (ref "COUT") (pin "1") (pinfunction "1_1") (pintype "passive"))
      (node (ref "RFBT") (pin "1") (pinfunction "1_1") (pintype "passive"))
      (node (ref "U2") (pin "6") (pinfunction "VOUT_6") (pintype "power_in"))
      (node (ref "U3") (pin "12") (pinfunction "VM_12") (pintype "power_in"))
    )
    (net (code "61") (name "unconnected-(ANT-PadP$3)") (class "Default")
      (node (ref "ANT") (pin "P$3") (pinfunction "P$3_P$3") (pintype "no_connect"))
    )
    (net (code "62") (name "unconnected-(ANT-PadP$4)") (class "Default")
      (node (ref "ANT") (pin "P$4") (pinfunction "P$4_P$4") (pintype "no_connect"))
    )
    (net (code "63") (name "unconnected-(D4-CKO-Pad2)") (class "Default")
      (node (ref "D4") (pin "2") (pinfunction "CKO_2") (pintype "output"))
    )
    (net (code "64") (name "unconnected-(D4-DO-Pad1)") (class "Default")
      (node (ref "D4") (pin "1") (pinfunction "DO_1") (pintype "output"))
    )
    (net (code "65") (name "unconnected-(ESP32A-CAP1_NC-Pad48)") (class "Default")
      (node (ref "ESP32") (pin "48") (pinfunction "CAP1_NC_48") (pintype "bidirectional"))
    )
    (net (code "66") (name "unconnected-(ESP32A-CAP2_NC-Pad47)") (class "Default")
      (node (ref "ESP32") (pin "47") (pinfunction "CAP2_NC_47") (pintype "bidirectional"))
    )
    (net (code "67") (name "unconnected-(ESP32A-IO4-Pad24)") (class "Default")
      (node (ref "ESP32") (pin "24") (pinfunction "IO4_24") (pintype "bidirectional"))
    )
    (net (code "68") (name "unconnected-(ESP32A-IO15-Pad21)") (class "Default")
      (node (ref "ESP32") (pin "21") (pinfunction "IO15_21") (pintype "bidirectional"))
    )
    (net (code "69") (name "unconnected-(ESP32A-IO16-Pad25)") (class "Default")
      (node (ref "ESP32") (pin "25") (pinfunction "IO16_25") (pintype "bidirectional"))
    )
    (net (code "70") (name "unconnected-(ESP32A-IO19-Pad38)") (class "Default")
      (node (ref "ESP32") (pin "38") (pinfunction "IO19_38") (pintype "bidirectional"))
    )
    (net (code "71") (name "unconnected-(ESP32A-IO23-Pad36)") (class "Default")
      (node (ref "ESP32") (pin "36") (pinfunction "IO23_36") (pintype "bidirectional"))
    )
    (net (code "72") (name "unconnected-(ESP32A-IO26-Pad15)") (class "Default")
      (node (ref "ESP32") (pin "15") (pinfunction "IO26_15") (pintype "bidirectional"))
    )
    (net (code "73") (name "unconnected-(ESP32A-IO32-Pad12)") (class "Default")
      (node (ref "ESP32") (pin "12") (pinfunction "IO32_12") (pintype "bidirectional"))
    )
    (net (code "74") (name "unconnected-(ESP32A-XTAL_N_NC-Pad44)") (class "Default")
      (node (ref "ESP32") (pin "44") (pinfunction "XTAL_N_NC_44") (pintype "bidirectional"))
    )
    (net (code "75") (name "unconnected-(ESP32A-XTAL_P_NC-Pad45)") (class "Default")
      (node (ref "ESP32") (pin "45") (pinfunction "XTAL_P_NC_45") (pintype "bidirectional"))
    )
    (net (code "76") (name "unconnected-(J1-ID-Pad4)") (class "Default")
      (node (ref "J1") (pin "4") (pinfunction "ID_4") (pintype "passive"))
    )
    (net (code "77") (name "unconnected-(LSM6-INT1-Pad4)") (class "Default")
      (node (ref "LSM6") (pin "4") (pinfunction "INT1_4") (pintype "bidirectional"))
    )
    (net (code "78") (name "unconnected-(LSM6-INT2-Pad9)") (class "Default")
      (node (ref "LSM6") (pin "9") (pinfunction "INT2_9") (pintype "bidirectional"))
    )
    (net (code "79") (name "unconnected-(LSM6-OCS_AUX-Pad10)") (class "Default")
      (node (ref "LSM6") (pin "10") (pinfunction "OCS_AUX_10") (pintype "bidirectional"))
    )
    (net (code "80") (name "unconnected-(LSM6-SDO_AUX-Pad11)") (class "Default")
      (node (ref "LSM6") (pin "11") (pinfunction "SDO_AUX_11") (pintype "bidirectional"))
    )
    (net (code "81") (name "unconnected-(U3-B_IN1-Pad9)") (class "Default")
      (node (ref "U3") (pin "9") (pinfunction "B_IN1_9") (pintype "input"))
    )
    (net (code "82") (name "unconnected-(U3-B_IN2-Pad10)") (class "Default")
      (node (ref "U3") (pin "10") (pinfunction "B_IN2_10") (pintype "input"))
    )
    (net (code "83") (name "unconnected-(U3-B_ISENSE-Pad6)") (class "Default")
      (node (ref "U3") (pin "6") (pinfunction "B_ISENSE_6") (pintype "bidirectional"))
    )
    (net (code "84") (name "unconnected-(U3-B_OUT1-Pad7)") (class "Default")
      (node (ref "U3") (pin "7") (pinfunction "B_OUT1_7") (pintype "output"))
    )
    (net (code "85") (name "unconnected-(U3-B_OUT2-Pad5)") (class "Default")
      (node (ref "U3") (pin "5") (pinfunction "B_OUT2_5") (pintype "output"))
    )
    (net (code "86") (name "unconnected-(U4A-#RST-Pad9)") (class "Default")
      (node (ref "U4") (pin "9") (pinfunction "#RST_9") (pintype "bidirectional"))
    )
    (net (code "87") (name "unconnected-(U4A-#SUSPEND-Pad15)") (class "Default")
      (node (ref "U4") (pin "15") (pinfunction "#SUSPEND_15") (pintype "output"))
    )
    (net (code "88") (name "unconnected-(U4A-CTS-Pad18)") (class "Default")
      (node (ref "U4") (pin "18") (pinfunction "CTS_18") (pintype "input"))
    )
    (net (code "89") (name "unconnected-(U4A-DCD-Pad24)") (class "Default")
      (node (ref "U4") (pin "24") (pinfunction "DCD_24") (pintype "input"))
    )
    (net (code "90") (name "unconnected-(U4A-DSR-Pad22)") (class "Default")
      (node (ref "U4") (pin "22") (pinfunction "DSR_22") (pintype "input"))
    )
    (net (code "91") (name "unconnected-(U4A-GPIO0{slash}TXLED-Pad14)") (class "Default")
      (node (ref "U4") (pin "14") (pinfunction "GPIO0/TXLED_14") (pintype "bidirectional"))
    )
    (net (code "92") (name "unconnected-(U4A-GPIO1{slash}RXLED-Pad13)") (class "Default")
      (node (ref "U4") (pin "13") (pinfunction "GPIO1/RXLED_13") (pintype "bidirectional"))
    )
    (net (code "93") (name "unconnected-(U4A-GPIO2-Pad12)") (class "Default")
      (node (ref "U4") (pin "12") (pinfunction "GPIO2_12") (pintype "bidirectional"))
    )
    (net (code "94") (name "unconnected-(U4A-GPIO3-Pad11)") (class "Default")
      (node (ref "U4") (pin "11") (pinfunction "GPIO3_11") (pintype "bidirectional"))
    )
    (net (code "95") (name "unconnected-(U4A-NC-Pad10)") (class "Default")
      (node (ref "U4") (pin "10") (pinfunction "NC_10") (pintype "no_connect"))
    )
    (net (code "96") (name "unconnected-(U4A-RI-Pad1)") (class "Default")
      (node (ref "U4") (pin "1") (pinfunction "RI_1") (pintype "input"))
    )
    (net (code "97") (name "unconnected-(U4A-SUSPEND-Pad17)") (class "Default")
      (node (ref "U4") (pin "17") (pinfunction "SUSPEND_17") (pintype "output"))
    )
    (net (code "98") (name "unconnected-(U4A-VPP-Pad16)") (class "Default")
      (node (ref "U4") (pin "16") (pinfunction "VPP_16") (pintype "bidirectional"))
    )
  )
)
